# PHT_logger.net
KiCad netlist of a schematic drawn in EAGLE
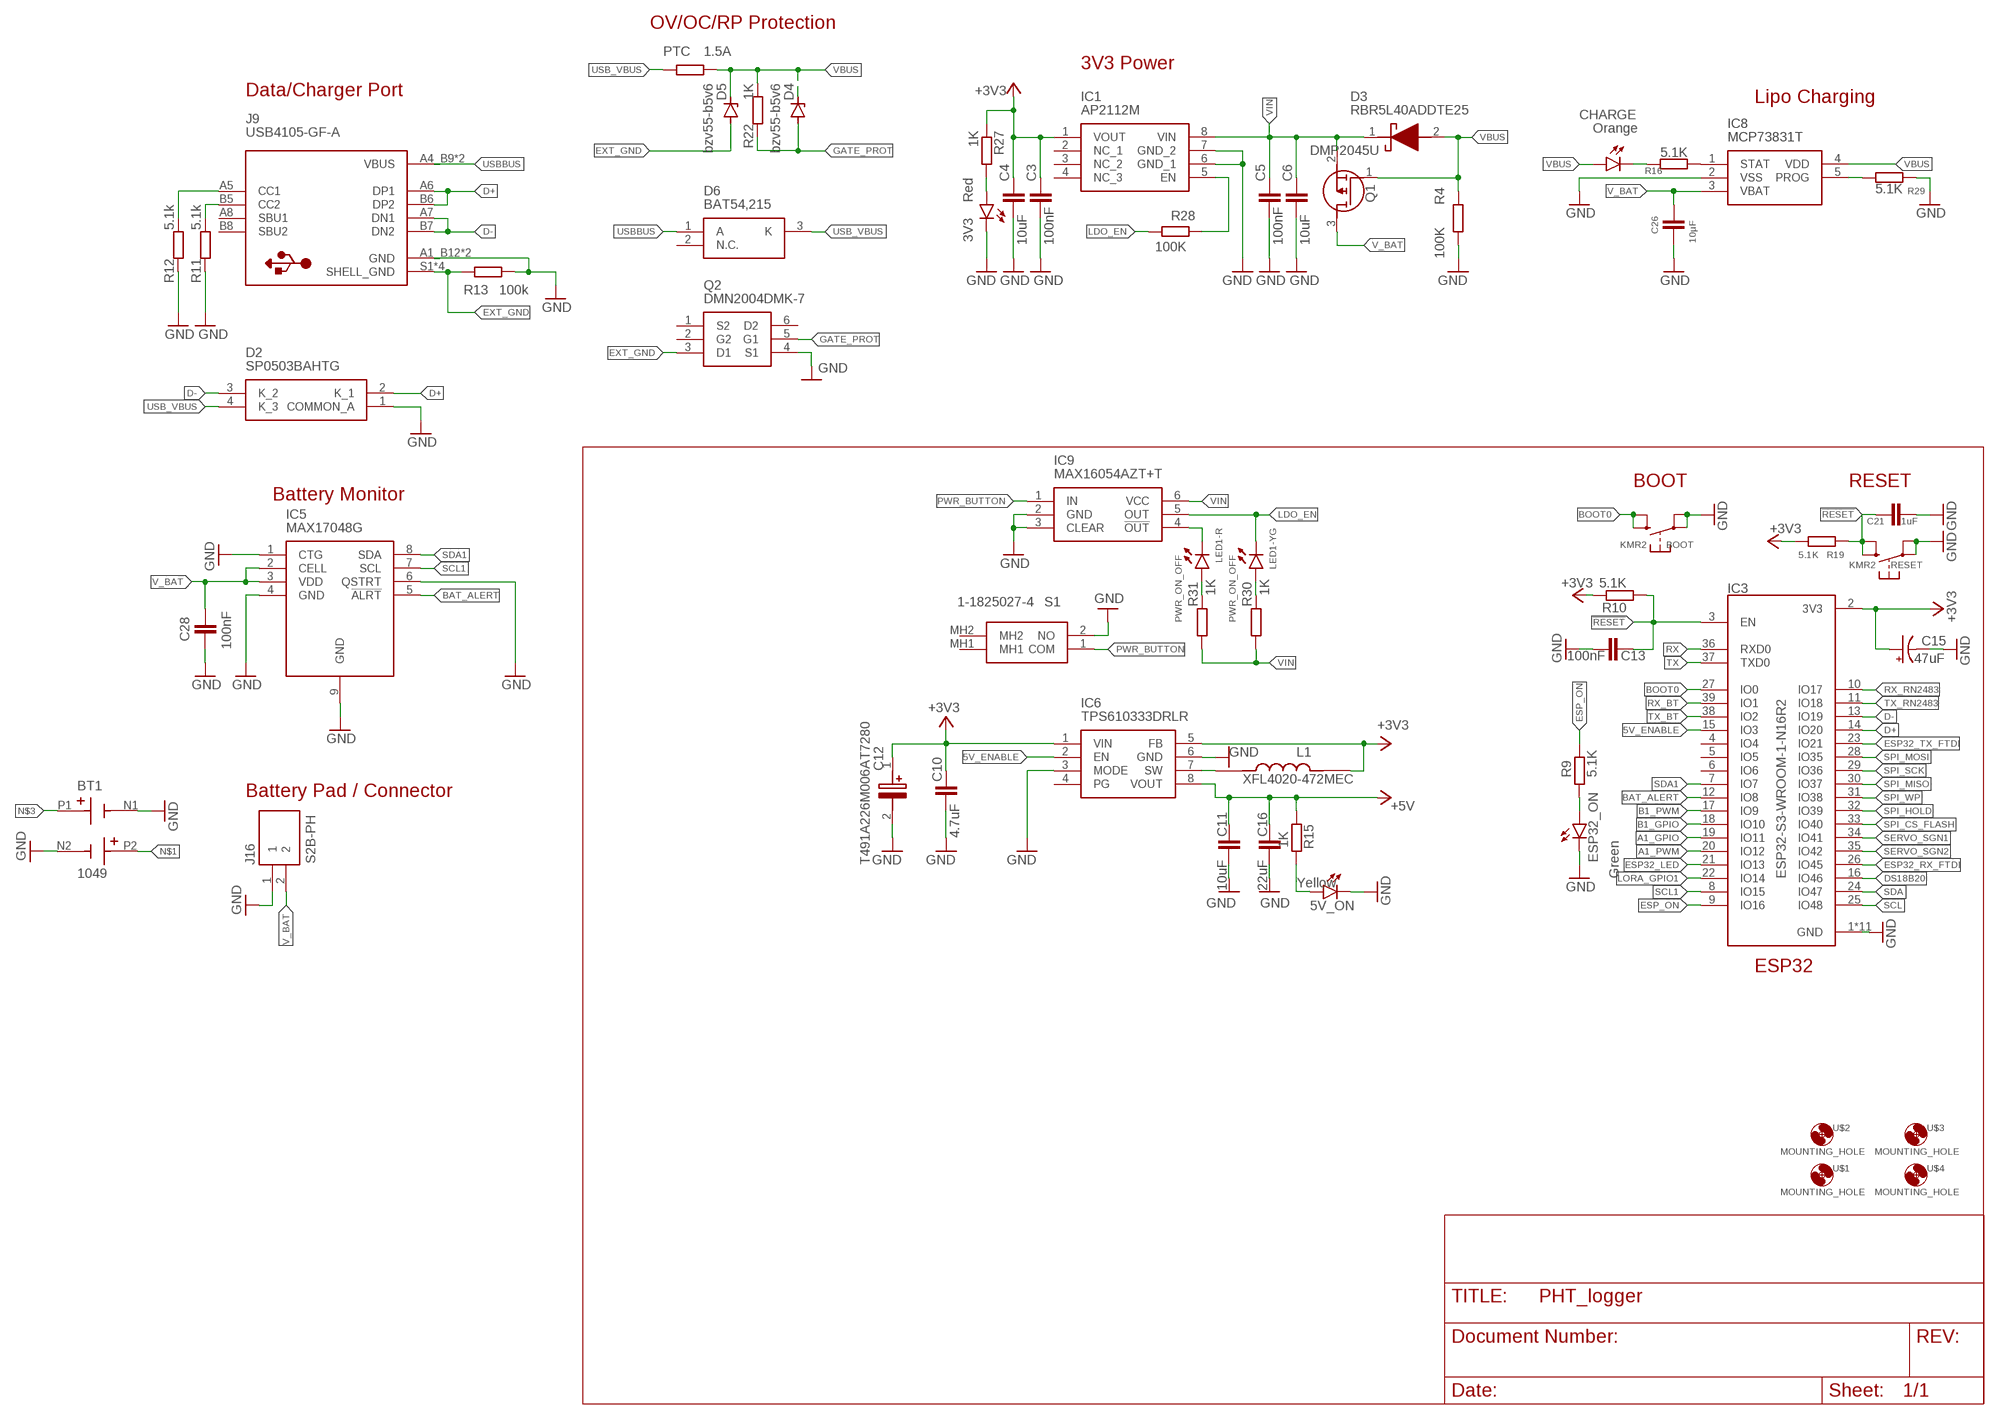
[diagram p0: schematic, sheet 1]

(export (version "E")
  (design (tool "Eeschema 10.0.6"))
  (components
    (comp (ref "3V3")
      (value "Red")
      (footprint "eagle-import:CHIPLED_0805")
      (libsource (lib "eagle-import") (part "LEDCHIPLED_0805"))
    )
    (comp (ref "5V_ON")
      (value "Yellow")
      (footprint "eagle-import:CHIPLED_0805")
      (libsource (lib "eagle-import") (part "LEDCHIPLED_0805"))
    )
    (comp (ref "BOOT")
      (value "KMR2")
      (footprint "eagle-import:BTN_KMR2_4.6X2.8")
      (libsource (lib "eagle-import") (part "SWITCH_TACT_SMT4.6X2.8"))
    )
    (comp (ref "BT1")
      (value "1049")
      (footprint "eagle-import:BAT_1049")
      (fields (field (name "MF") "Keystone Electronics"))
      (libsource (lib "eagle-import") (part "1049"))
    )
    (comp (ref "C3")
      (value "100nF")
      (footprint "eagle-import:C0603")
      (libsource (lib "eagle-import") (part "C-EUC0603"))
    )
    (comp (ref "C4")
      (value "10uF")
      (footprint "eagle-import:C0603")
      (libsource (lib "eagle-import") (part "C-EUC0603"))
    )
    (comp (ref "C5")
      (value "100nF")
      (footprint "eagle-import:C0603")
      (libsource (lib "eagle-import") (part "C-EUC0603"))
    )
    (comp (ref "C6")
      (value "10uF")
      (footprint "eagle-import:C0603")
      (libsource (lib "eagle-import") (part "C-EUC0603"))
    )
    (comp (ref "C10")
      (value "4.7uF")
      (footprint "eagle-import:C0805")
      (libsource (lib "eagle-import") (part "C-EUC0805"))
    )
    (comp (ref "C11")
      (value "10uF")
      (footprint "eagle-import:C0805")
      (libsource (lib "eagle-import") (part "C-EUC0805"))
    )
    (comp (ref "C12")
      (value "T491A226M006AT7280")
      (footprint "eagle-import:T491A")
      (libsource (lib "eagle-import") (part "T491A226M006AT7280"))
    )
    (comp (ref "C13")
      (value "100nF")
      (footprint "eagle-import:C0603")
      (libsource (lib "eagle-import") (part "C-EUC0603"))
    )
    (comp (ref "C15")
      (value "47uF")
      (footprint "eagle-import:CAPMP6032X250N")
      (fields (field (name "MF") "Vishay") (field (name "MP") "293D226X9025C2TE3"))
      (libsource (lib "eagle-import") (part "293D226X9025C2TE3"))
    )
    (comp (ref "C16")
      (value "22uF")
      (footprint "eagle-import:C0805")
      (libsource (lib "eagle-import") (part "C-EUC0805"))
    )
    (comp (ref "C21")
      (value "1uF")
      (footprint "eagle-import:C0603")
      (libsource (lib "eagle-import") (part "C-EUC0603"))
    )
    (comp (ref "C26")
      (value "10µF")
      (footprint "eagle-import:C0603K")
      (libsource (lib "eagle-import") (part "C-EUC0603K"))
    )
    (comp (ref "C28")
      (value "100nF")
      (footprint "eagle-import:C0603")
      (libsource (lib "eagle-import") (part "C-EUC0603"))
    )
    (comp (ref "CHARGE")
      (value "Orange")
      (footprint "eagle-import:CHIPLED_0805")
      (libsource (lib "eagle-import") (part "LEDCHIPLED_0805"))
    )
    (comp (ref "D2")
      (value "SP0503BAHTG")
      (footprint "eagle-import:SP0503BAHTG")
      (fields (field (name "MOUSER_PART_NUMBER") "576-SP0503BAHTG"))
      (libsource (lib "eagle-import") (part "SP0503BAHTG"))
    )
    (comp (ref "D3")
      (value "RBR5L40ADDTE25")
      (footprint "eagle-import:DIOM5026X220N")
      (fields (field (name "MOUSER_PART_NUMBER") "755-RBR5L40ADDTE25"))
      (libsource (lib "eagle-import") (part "RBR5L40ADDTE25"))
    )
    (comp (ref "D4")
      (value "bzv55-b5v6")
      (footprint "eagle-import:SOD80C")
      (libsource (lib "eagle-import") (part "ZENER-DIODESOD80C"))
    )
    (comp (ref "D5")
      (value "bzv55-b5v6")
      (footprint "eagle-import:SOD80C")
      (libsource (lib "eagle-import") (part "ZENER-DIODESOD80C"))
    )
    (comp (ref "D6")
      (value "BAT54,215")
      (footprint "eagle-import:SOT95P230X110-3N")
      (fields (field (name "MOUSER_PART_NUMBER") "771-BAT54-T/R"))
      (libsource (lib "eagle-import") (part "BAT54,215"))
    )
    (comp (ref "ESP32_ON")
      (value "Green")
      (footprint "eagle-import:CHIPLED_0805")
      (libsource (lib "eagle-import") (part "LEDCHIPLED_0805"))
    )
    (comp (ref "IC1")
      (value "AP2112M")
      (footprint "eagle-import:SOIC127P600X170-8N")
      (fields
        (field (name "MANUFACTURER_PART_NUMBER") "AP2112M-3.3TRG1")
        (field (name "MOUSER_PART_NUMBER") "621-AP2112M-3.3TRG1")
      )
      (libsource (lib "eagle-import") (part "AP2112M-3.3TRG1"))
    )
    (comp (ref "IC3")
      (value "ESP32-S3-WROOM-1-N16R2")
      (footprint "eagle-import:XCVR_ESP32-S3-WROOM-1-N16R2")
      (fields (field (name "MF") "Espressif Systems") (field (name "SPICEPREFIX") "X"))
      (libsource (lib "eagle-import") (part "ESP32-S3-WROOM-1-N16R2"))
    )
    (comp (ref "IC5")
      (value "MAX17048G")
      (footprint "eagle-import:SON50P200X200X80-9N")
      (fields
        (field (name "MANUFACTURER_PART_NUMBER") "MAX17048G+T10")
        (field (name "MOUSER_PART_NUMBER") "700-MAX17048G+T10")
      )
      (libsource (lib "eagle-import") (part "MAX17048G+T10"))
    )
    (comp (ref "IC6")
      (value "TPS610333DRLR")
      (footprint "eagle-import:SOTFL50P160X60-8N")
      (fields (field (name "MOUSER_PART_NUMBER") "595-TPS610333DRLR"))
      (libsource (lib "eagle-import") (part "TPS610333DRLR"))
    )
    (comp (ref "IC8")
      (value "MCP73831T")
      (footprint "eagle-import:SOT95P270X145-5N")
      (fields
        (field (name "MANUFACTURER_PART_NUMBER") "MCP73831T-2ACI/OT")
        (field (name "MOUSER_PART_NUMBER") "579-MCP73831T-2ACIOT")
      )
      (libsource (lib "eagle-import") (part "MCP73831T-2ACI_OT"))
    )
    (comp (ref "IC9")
      (value "MAX16054AZT+T")
      (footprint "eagle-import:SOT95P275X110-6N")
      (fields (field (name "MOUSER_PART_NUMBER") "700-MAX16054AZTT"))
      (libsource (lib "eagle-import") (part "MAX16054AZT+T"))
    )
    (comp (ref "J9")
      (value "USB4105-GF-A")
      (footprint "eagle-import:GCT_USB4105-GF-A")
      (fields (field (name "MF") "GCT"))
      (libsource (lib "eagle-import") (part "USB4105-GF-A"))
    )
    (comp (ref "J16")
      (value "S2B-PH")
      (footprint "eagle-import:JST_S2B-PH-K-S(LF)(SN)")
      (fields (field (name "MF") "JST Sales America Inc.") (field (name "MP") "S2B-PH-K-S(LF)(SN)"))
      (libsource (lib "eagle-import") (part "S2B-PH-K-S(LF)(SN)"))
    )
    (comp (ref "L1")
      (value "XFL4020-472MEC")
      (footprint "eagle-import:IND_XFL4020-472MEC")
      (fields (field (name "MF") "Coilcraft"))
      (libsource (lib "eagle-import") (part "XFL4020-472MEC"))
    )
    (comp (ref "LED1")
      (value "PWR_ON_OFF")
      (footprint "eagle-import:3216(1206)-4")
      (fields (field (name "MF") "OptoSupply") (field (name "MP") "OSRG1206C1C"))
      (libsource (lib "eagle-import") (part "OSRG1206C1C"))
    )
    (comp (ref "PTC")
      (value "1.5A")
      (footprint "eagle-import:R2512")
      (libsource (lib "eagle-import") (part "R-EU_R2512"))
    )
    (comp (ref "Q1")
      (value "DMP2045U")
      (footprint "eagle-import:SOT96P240X110-3N")
      (fields
        (field (name "MANUFACTURER_PART_NUMBER") "DMP2045U-7")
        (field (name "MOUSER_PART_NUMBER") "621-DMP2045U-7")
      )
      (libsource (lib "eagle-import") (part "DMP2045U-7"))
    )
    (comp (ref "Q2")
      (value "DMN2004DMK-7")
      (footprint "eagle-import:SOT95P285X145-6N")
      (fields (field (name "MOUSER_PART_NUMBER") "621-DMN2004DMK-7"))
      (libsource (lib "eagle-import") (part "DMN2004DMK-7"))
    )
    (comp (ref "R4")
      (value "100K")
      (footprint "eagle-import:R0603")
      (libsource (lib "eagle-import") (part "R-EU_R0603"))
    )
    (comp (ref "R9")
      (value "5.1K")
      (footprint "eagle-import:R0603")
      (libsource (lib "eagle-import") (part "R-EU_R0603"))
    )
    (comp (ref "R10")
      (value "5.1K")
      (footprint "eagle-import:R0603")
      (libsource (lib "eagle-import") (part "R-EU_R0603"))
    )
    (comp (ref "R11")
      (value "5.1k")
      (footprint "eagle-import:R0603")
      (libsource (lib "eagle-import") (part "R-EU_R0603"))
    )
    (comp (ref "R12")
      (value "5.1k")
      (footprint "eagle-import:R0603")
      (libsource (lib "eagle-import") (part "R-EU_R0603"))
    )
    (comp (ref "R13")
      (value "100k")
      (footprint "eagle-import:R0603")
      (libsource (lib "eagle-import") (part "R-EU_R0603"))
    )
    (comp (ref "R15")
      (value "1K")
      (footprint "eagle-import:R0603")
      (libsource (lib "eagle-import") (part "R-EU_R0603"))
    )
    (comp (ref "R16")
      (value "5.1K")
      (footprint "eagle-import:R0603")
      (libsource (lib "eagle-import") (part "R-EU_R0603"))
    )
    (comp (ref "R19")
      (value "5.1K")
      (footprint "eagle-import:R0603")
      (libsource (lib "eagle-import") (part "R-EU_R0603"))
    )
    (comp (ref "R22")
      (value "1K")
      (footprint "eagle-import:R0603")
      (libsource (lib "eagle-import") (part "R-EU_R0603"))
    )
    (comp (ref "R27")
      (value "1K")
      (footprint "eagle-import:R0603")
      (libsource (lib "eagle-import") (part "R-EU_R0603"))
    )
    (comp (ref "R28")
      (value "100K")
      (footprint "eagle-import:R0603")
      (libsource (lib "eagle-import") (part "R-EU_R0603"))
    )
    (comp (ref "R29")
      (value "5.1K")
      (footprint "eagle-import:R0603")
      (libsource (lib "eagle-import") (part "R-EU_R0603"))
    )
    (comp (ref "R30")
      (value "1K")
      (footprint "eagle-import:R0603")
      (libsource (lib "eagle-import") (part "R-EU_R0603"))
    )
    (comp (ref "R31")
      (value "1K")
      (footprint "eagle-import:R0603")
      (libsource (lib "eagle-import") (part "R-EU_R0603"))
    )
    (comp (ref "RESET")
      (value "KMR2")
      (footprint "eagle-import:BTN_KMR2_4.6X2.8")
      (libsource (lib "eagle-import") (part "SWITCH_TACT_SMT4.6X2.8"))
    )
    (comp (ref "S1")
      (value "1-1825027-4")
      (footprint "eagle-import:118250274")
      (libsource (lib "eagle-import") (part "1-1825027-4"))
    )
    (comp (ref "U$1")
      (value "MOUNTING_HOLE")
      (footprint "eagle-import:MOUNTING_HOLE")
      (libsource (lib "eagle-import") (part "MOUNTING_HOLE"))
    )
    (comp (ref "U$2")
      (value "MOUNTING_HOLE")
      (footprint "eagle-import:MOUNTING_HOLE")
      (libsource (lib "eagle-import") (part "MOUNTING_HOLE"))
    )
    (comp (ref "U$3")
      (value "MOUNTING_HOLE")
      (footprint "eagle-import:MOUNTING_HOLE")
      (libsource (lib "eagle-import") (part "MOUNTING_HOLE"))
    )
    (comp (ref "U$4")
      (value "MOUNTING_HOLE")
      (footprint "eagle-import:MOUNTING_HOLE")
      (libsource (lib "eagle-import") (part "MOUNTING_HOLE"))
    )
  )
  (nets
    (net (code "1") (name "+3V3") (class "Default")
      (node (ref "C10") (pin "2") (pinfunction "2_2") (pintype "passive"))
      (node (ref "C12") (pin "1") (pinfunction "+_1") (pintype "bidirectional"))
      (node (ref "C15") (pin "1") (pinfunction "+_1") (pintype "passive"))
      (node (ref "C3") (pin "2") (pinfunction "2_2") (pintype "passive"))
      (node (ref "C4") (pin "2") (pinfunction "2_2") (pintype "passive"))
      (node (ref "IC1") (pin "1") (pinfunction "VOUT_1") (pintype "bidirectional"))
      (node (ref "IC3") (pin "2") (pinfunction "3V3_2") (pintype "power_in"))
      (node (ref "IC6") (pin "1") (pinfunction "VIN_1") (pintype "bidirectional"))
      (node (ref "IC6") (pin "5") (pinfunction "FB_5") (pintype "bidirectional"))
      (node (ref "L1") (pin "2") (pinfunction "2_2") (pintype "passive"))
      (node (ref "R10") (pin "2") (pinfunction "2_2") (pintype "passive"))
      (node (ref "R19") (pin "2") (pinfunction "2_2") (pintype "passive"))
      (node (ref "R27") (pin "1") (pinfunction "1_1") (pintype "passive"))
    )
    (net (code "2") (name "+5V") (class "Default")
      (node (ref "C11") (pin "2") (pinfunction "2_2") (pintype "passive"))
      (node (ref "C16") (pin "2") (pinfunction "2_2") (pintype "passive"))
      (node (ref "IC6") (pin "8") (pinfunction "VOUT_8") (pintype "bidirectional"))
      (node (ref "R15") (pin "1") (pinfunction "1_1") (pintype "passive"))
    )
    (net (code "3") (name "/~{RESET}") (class "Default")
      (node (ref "C13") (pin "1") (pinfunction "1_1") (pintype "passive"))
      (node (ref "C21") (pin "1") (pinfunction "1_1") (pintype "passive"))
      (node (ref "IC3") (pin "3") (pinfunction "EN_3") (pintype "input"))
      (node (ref "R10") (pin "1") (pinfunction "1_1") (pintype "passive"))
      (node (ref "R19") (pin "1") (pinfunction "1_1") (pintype "passive"))
      (node (ref "RESET") (pin "B") (pinfunction "S_B") (pintype "passive"))
      (node (ref "RESET") (pin "B'") (pinfunction "S1_B'") (pintype "passive"))
    )
    (net (code "4") (name "5V_ENABLE") (class "Default")
      (node (ref "IC3") (pin "15") (pinfunction "IO3_15") (pintype "bidirectional"))
      (node (ref "IC6") (pin "2") (pinfunction "EN_2") (pintype "bidirectional"))
    )
    (net (code "5") (name "A1_GPIO") (class "Default")
      (node (ref "IC3") (pin "19") (pinfunction "IO11_19") (pintype "bidirectional"))
    )
    (net (code "6") (name "A1_PWM") (class "Default")
      (node (ref "IC3") (pin "20") (pinfunction "IO12_20") (pintype "bidirectional"))
    )
    (net (code "7") (name "B1_GPIO") (class "Default")
      (node (ref "IC3") (pin "18") (pinfunction "IO10_18") (pintype "bidirectional"))
    )
    (net (code "8") (name "B1_PWM") (class "Default")
      (node (ref "IC3") (pin "17") (pinfunction "IO9_17") (pintype "bidirectional"))
    )
    (net (code "9") (name "BAT_ALERT") (class "Default")
      (node (ref "IC3") (pin "12") (pinfunction "IO8_12") (pintype "bidirectional"))
      (node (ref "IC5") (pin "5") (pinfunction "~{ALRT}_5") (pintype "bidirectional"))
    )
    (net (code "10") (name "BOOT0") (class "Default")
      (node (ref "BOOT") (pin "B") (pinfunction "S_B") (pintype "passive"))
      (node (ref "BOOT") (pin "B'") (pinfunction "S1_B'") (pintype "passive"))
      (node (ref "IC3") (pin "27") (pinfunction "IO0_27") (pintype "bidirectional"))
    )
    (net (code "11") (name "D+") (class "Default")
      (node (ref "D2") (pin "2") (pinfunction "K_1_2") (pintype "bidirectional"))
      (node (ref "IC3") (pin "14") (pinfunction "IO20_14") (pintype "bidirectional"))
      (node (ref "J9") (pin "A6") (pinfunction "DP1_A6") (pintype "bidirectional"))
      (node (ref "J9") (pin "B6") (pinfunction "DP2_B6") (pintype "bidirectional"))
    )
    (net (code "12") (name "D-") (class "Default")
      (node (ref "D2") (pin "3") (pinfunction "K_2_3") (pintype "bidirectional"))
      (node (ref "IC3") (pin "13") (pinfunction "IO19_13") (pintype "bidirectional"))
      (node (ref "J9") (pin "A7") (pinfunction "DN1_A7") (pintype "bidirectional"))
      (node (ref "J9") (pin "B7") (pinfunction "DN2_B7") (pintype "bidirectional"))
    )
    (net (code "13") (name "DS18B20") (class "Default")
      (node (ref "IC3") (pin "16") (pinfunction "IO46_16") (pintype "bidirectional"))
    )
    (net (code "14") (name "ESP32_LED") (class "Default")
      (node (ref "IC3") (pin "21") (pinfunction "IO13_21") (pintype "bidirectional"))
    )
    (net (code "15") (name "ESP32_RX_FTDI") (class "Default")
      (node (ref "IC3") (pin "26") (pinfunction "IO45_26") (pintype "bidirectional"))
    )
    (net (code "16") (name "ESP32_TX_FTDI") (class "Default")
      (node (ref "IC3") (pin "23") (pinfunction "IO21_23") (pintype "bidirectional"))
    )
    (net (code "17") (name "ESP_ON") (class "Default")
      (node (ref "IC3") (pin "9") (pinfunction "IO16_9") (pintype "bidirectional"))
      (node (ref "R9") (pin "2") (pinfunction "2_2") (pintype "passive"))
    )
    (net (code "18") (name "EXT_GND") (class "Default")
      (node (ref "D5") (pin "A") (pinfunction "A_A") (pintype "passive"))
      (node (ref "J9") (pin "S1") (pinfunction "SHELL_GND_S1") (pintype "power_in"))
      (node (ref "J9") (pin "S2") (pinfunction "SHELL_GND_S2") (pintype "power_in"))
      (node (ref "J9") (pin "S3") (pinfunction "SHELL_GND_S3") (pintype "power_in"))
      (node (ref "J9") (pin "S4") (pinfunction "SHELL_GND_S4") (pintype "power_in"))
      (node (ref "Q2") (pin "3") (pinfunction "D1_3") (pintype "bidirectional"))
      (node (ref "R13") (pin "2") (pinfunction "2_2") (pintype "passive"))
    )
    (net (code "19") (name "GATE_PROT") (class "Default")
      (node (ref "D4") (pin "A") (pinfunction "A_A") (pintype "passive"))
      (node (ref "Q2") (pin "5") (pinfunction "G1_5") (pintype "bidirectional"))
      (node (ref "R22") (pin "1") (pinfunction "1_1") (pintype "passive"))
    )
    (net (code "20") (name "GND") (class "Default")
      (node (ref "3V3") (pin "C") (pinfunction "C_C") (pintype "passive"))
      (node (ref "5V_ON") (pin "C") (pinfunction "C_C") (pintype "passive"))
      (node (ref "BOOT") (pin "A") (pinfunction "P_A") (pintype "passive"))
      (node (ref "BOOT") (pin "A'") (pinfunction "P1_A'") (pintype "passive"))
      (node (ref "BT1") (pin "N1") (pinfunction "NEG1_N1") (pintype "passive"))
      (node (ref "BT1") (pin "N2") (pinfunction "NEG2_N2") (pintype "passive"))
      (node (ref "C10") (pin "1") (pinfunction "1_1") (pintype "passive"))
      (node (ref "C11") (pin "1") (pinfunction "1_1") (pintype "passive"))
      (node (ref "C12") (pin "2") (pinfunction "-_2") (pintype "bidirectional"))
      (node (ref "C13") (pin "2") (pinfunction "2_2") (pintype "passive"))
      (node (ref "C15") (pin "2") (pinfunction "-_2") (pintype "passive"))
      (node (ref "C16") (pin "1") (pinfunction "1_1") (pintype "passive"))
      (node (ref "C21") (pin "2") (pinfunction "2_2") (pintype "passive"))
      (node (ref "C26") (pin "2") (pinfunction "2_2") (pintype "passive"))
      (node (ref "C28") (pin "2") (pinfunction "2_2") (pintype "passive"))
      (node (ref "C3") (pin "1") (pinfunction "1_1") (pintype "passive"))
      (node (ref "C4") (pin "1") (pinfunction "1_1") (pintype "passive"))
      (node (ref "C5") (pin "1") (pinfunction "1_1") (pintype "passive"))
      (node (ref "C6") (pin "1") (pinfunction "1_1") (pintype "passive"))
      (node (ref "D2") (pin "1") (pinfunction "COMMON_A_1") (pintype "bidirectional"))
      (node (ref "ESP32_ON") (pin "C") (pinfunction "C_C") (pintype "passive"))
      (node (ref "IC1") (pin "6") (pinfunction "GND_1_6") (pintype "bidirectional"))
      (node (ref "IC1") (pin "7") (pinfunction "GND_2_7") (pintype "bidirectional"))
      (node (ref "IC3") (pin "1") (pinfunction "GND_1") (pintype "power_in"))
      (node (ref "IC3") (pin "40") (pinfunction "GND_40") (pintype "power_in"))
      (node (ref "IC3") (pin "41_1") (pinfunction "GND_41_1") (pintype "power_in"))
      (node (ref "IC3") (pin "41_2") (pinfunction "GND_41_2") (pintype "power_in"))
      (node (ref "IC3") (pin "41_3") (pinfunction "GND_41_3") (pintype "power_in"))
      (node (ref "IC3") (pin "41_4") (pinfunction "GND_41_4") (pintype "power_in"))
      (node (ref "IC3") (pin "41_5") (pinfunction "GND_41_5") (pintype "power_in"))
      (node (ref "IC3") (pin "41_6") (pinfunction "GND_41_6") (pintype "power_in"))
      (node (ref "IC3") (pin "41_7") (pinfunction "GND_41_7") (pintype "power_in"))
      (node (ref "IC3") (pin "41_8") (pinfunction "GND_41_8") (pintype "power_in"))
      (node (ref "IC3") (pin "41_9") (pinfunction "GND_41_9") (pintype "power_in"))
      (node (ref "IC5") (pin "1") (pinfunction "CTG_1") (pintype "bidirectional"))
      (node (ref "IC5") (pin "4") (pinfunction "GND_4") (pintype "bidirectional"))
      (node (ref "IC5") (pin "6") (pinfunction "QSTRT_6") (pintype "bidirectional"))
      (node (ref "IC5") (pin "9") (pinfunction "GND_9") (pintype "bidirectional"))
      (node (ref "IC6") (pin "3") (pinfunction "MODE_3") (pintype "bidirectional"))
      (node (ref "IC6") (pin "6") (pinfunction "GND_6") (pintype "bidirectional"))
      (node (ref "IC8") (pin "2") (pinfunction "VSS_2") (pintype "bidirectional"))
      (node (ref "IC9") (pin "2") (pinfunction "GND_2") (pintype "bidirectional"))
      (node (ref "IC9") (pin "3") (pinfunction "CLEAR_3") (pintype "bidirectional"))
      (node (ref "J16") (pin "1") (pinfunction "1_1") (pintype "passive"))
      (node (ref "J9") (pin "A1_B12") (pinfunction "GND_A1_B12") (pintype "power_in"))
      (node (ref "J9") (pin "B1_A12") (pinfunction "GND_B1_A12") (pintype "power_in"))
      (node (ref "Q2") (pin "4") (pinfunction "S1_4") (pintype "bidirectional"))
      (node (ref "R11") (pin "1") (pinfunction "1_1") (pintype "passive"))
      (node (ref "R12") (pin "1") (pinfunction "1_1") (pintype "passive"))
      (node (ref "R13") (pin "1") (pinfunction "1_1") (pintype "passive"))
      (node (ref "R29") (pin "1") (pinfunction "1_1") (pintype "passive"))
      (node (ref "R4") (pin "2") (pinfunction "2_2") (pintype "passive"))
      (node (ref "RESET") (pin "A") (pinfunction "P_A") (pintype "passive"))
      (node (ref "RESET") (pin "A'") (pinfunction "P1_A'") (pintype "passive"))
      (node (ref "S1") (pin "2") (pinfunction "NO_2") (pintype "bidirectional"))
    )
    (net (code "21") (name "LDO_EN") (class "Default")
      (node (ref "IC9") (pin "5") (pinfunction "OUT_5") (pintype "bidirectional"))
      (node (ref "LED1") (pin "3") (pinfunction "C_3") (pintype "output"))
      (node (ref "R28") (pin "1") (pinfunction "1_1") (pintype "passive"))
    )
    (net (code "22") (name "LORA_GPIO1") (class "Default")
      (node (ref "IC3") (pin "22") (pinfunction "IO14_22") (pintype "bidirectional"))
    )
    (net (code "23") (name "N$1") (class "Default")
      (node (ref "BT1") (pin "P2") (pinfunction "POS2_P2") (pintype "passive"))
    )
    (net (code "24") (name "N$3") (class "Default")
      (node (ref "BT1") (pin "P1") (pinfunction "POS1_P1") (pintype "passive"))
    )
    (net (code "25") (name "Net-(3V3-PadA)") (class "Default")
      (node (ref "3V3") (pin "A") (pinfunction "A_A") (pintype "passive"))
      (node (ref "R27") (pin "2") (pinfunction "2_2") (pintype "passive"))
    )
    (net (code "26") (name "Net-(5V_ON-PadA)") (class "Default")
      (node (ref "5V_ON") (pin "A") (pinfunction "A_A") (pintype "passive"))
      (node (ref "R15") (pin "2") (pinfunction "2_2") (pintype "passive"))
    )
    (net (code "27") (name "Net-(CHARGE-PadC)") (class "Default")
      (node (ref "CHARGE") (pin "C") (pinfunction "C_C") (pintype "passive"))
      (node (ref "R16") (pin "1") (pinfunction "1_1") (pintype "passive"))
    )
    (net (code "28") (name "Net-(ESP32_ON-PadA)") (class "Default")
      (node (ref "ESP32_ON") (pin "A") (pinfunction "A_A") (pintype "passive"))
      (node (ref "R9") (pin "1") (pinfunction "1_1") (pintype "passive"))
    )
    (net (code "29") (name "Net-(IC1-EN)") (class "Default")
      (node (ref "IC1") (pin "5") (pinfunction "EN_5") (pintype "bidirectional"))
      (node (ref "R28") (pin "2") (pinfunction "2_2") (pintype "passive"))
    )
    (net (code "30") (name "Net-(IC6-SW)") (class "Default")
      (node (ref "IC6") (pin "7") (pinfunction "SW_7") (pintype "bidirectional"))
      (node (ref "L1") (pin "1") (pinfunction "1_1") (pintype "passive"))
    )
    (net (code "31") (name "Net-(IC8-PROG)") (class "Default")
      (node (ref "IC8") (pin "5") (pinfunction "PROG_5") (pintype "bidirectional"))
      (node (ref "R29") (pin "2") (pinfunction "2_2") (pintype "passive"))
    )
    (net (code "32") (name "Net-(IC8-STAT)") (class "Default")
      (node (ref "IC8") (pin "1") (pinfunction "STAT_1") (pintype "bidirectional"))
      (node (ref "R16") (pin "2") (pinfunction "2_2") (pintype "passive"))
    )
    (net (code "33") (name "Net-(IC9-~{OUT})") (class "Default")
      (node (ref "IC9") (pin "4") (pinfunction "~{OUT}_4") (pintype "bidirectional"))
      (node (ref "LED1") (pin "1") (pinfunction "C_1") (pintype "output"))
    )
    (net (code "34") (name "Net-(J9-CC1)") (class "Default")
      (node (ref "J9") (pin "A5") (pinfunction "CC1_A5") (pintype "bidirectional"))
      (node (ref "R12") (pin "2") (pinfunction "2_2") (pintype "passive"))
    )
    (net (code "35") (name "Net-(J9-CC2)") (class "Default")
      (node (ref "J9") (pin "B5") (pinfunction "CC2_B5") (pintype "bidirectional"))
      (node (ref "R11") (pin "2") (pinfunction "2_2") (pintype "passive"))
    )
    (net (code "36") (name "Net-(LED1A-A)") (class "Default")
      (node (ref "LED1") (pin "2") (pinfunction "A_2") (pintype "input"))
      (node (ref "R31") (pin "2") (pinfunction "2_2") (pintype "passive"))
    )
    (net (code "37") (name "Net-(LED1B-A)") (class "Default")
      (node (ref "LED1") (pin "4") (pinfunction "A_4") (pintype "input"))
      (node (ref "R30") (pin "2") (pinfunction "2_2") (pintype "passive"))
    )
    (net (code "38") (name "PWR_BUTTON") (class "Default")
      (node (ref "IC9") (pin "1") (pinfunction "IN_1") (pintype "bidirectional"))
      (node (ref "S1") (pin "1") (pinfunction "COM_1") (pintype "bidirectional"))
    )
    (net (code "39") (name "RX") (class "Default")
      (node (ref "IC3") (pin "36") (pinfunction "RXD0_36") (pintype "bidirectional"))
    )
    (net (code "40") (name "RX_BT") (class "Default")
      (node (ref "IC3") (pin "39") (pinfunction "IO1_39") (pintype "bidirectional"))
    )
    (net (code "41") (name "RX_RN2483") (class "Default")
      (node (ref "IC3") (pin "10") (pinfunction "IO17_10") (pintype "bidirectional"))
    )
    (net (code "42") (name "SCL") (class "Default")
      (node (ref "IC3") (pin "25") (pinfunction "IO48_25") (pintype "bidirectional"))
    )
    (net (code "43") (name "SCL1") (class "Default")
      (node (ref "IC3") (pin "8") (pinfunction "IO15_8") (pintype "bidirectional"))
      (node (ref "IC5") (pin "7") (pinfunction "SCL_7") (pintype "bidirectional"))
    )
    (net (code "44") (name "SDA") (class "Default")
      (node (ref "IC3") (pin "24") (pinfunction "IO47_24") (pintype "bidirectional"))
    )
    (net (code "45") (name "SDA1") (class "Default")
      (node (ref "IC3") (pin "7") (pinfunction "IO7_7") (pintype "bidirectional"))
      (node (ref "IC5") (pin "8") (pinfunction "SDA_8") (pintype "bidirectional"))
    )
    (net (code "46") (name "SERVO_SGN1") (class "Default")
      (node (ref "IC3") (pin "34") (pinfunction "IO41_34") (pintype "bidirectional"))
    )
    (net (code "47") (name "SERVO_SGN2") (class "Default")
      (node (ref "IC3") (pin "35") (pinfunction "IO42_35") (pintype "bidirectional"))
    )
    (net (code "48") (name "SPI_CS_FLASH") (class "Default")
      (node (ref "IC3") (pin "33") (pinfunction "IO40_33") (pintype "bidirectional"))
    )
    (net (code "49") (name "SPI_HOLD") (class "Default")
      (node (ref "IC3") (pin "32") (pinfunction "IO39_32") (pintype "bidirectional"))
    )
    (net (code "50") (name "SPI_MISO") (class "Default")
      (node (ref "IC3") (pin "30") (pinfunction "IO37_30") (pintype "bidirectional"))
    )
    (net (code "51") (name "SPI_MOSI") (class "Default")
      (node (ref "IC3") (pin "28") (pinfunction "IO35_28") (pintype "bidirectional"))
    )
    (net (code "52") (name "SPI_SCK") (class "Default")
      (node (ref "IC3") (pin "29") (pinfunction "IO36_29") (pintype "bidirectional"))
    )
    (net (code "53") (name "SPI_WP") (class "Default")
      (node (ref "IC3") (pin "31") (pinfunction "IO38_31") (pintype "bidirectional"))
    )
    (net (code "54") (name "TX") (class "Default")
      (node (ref "IC3") (pin "37") (pinfunction "TXD0_37") (pintype "bidirectional"))
    )
    (net (code "55") (name "TX_BT") (class "Default")
      (node (ref "IC3") (pin "38") (pinfunction "IO2_38") (pintype "bidirectional"))
    )
    (net (code "56") (name "TX_RN2483") (class "Default")
      (node (ref "IC3") (pin "11") (pinfunction "IO18_11") (pintype "bidirectional"))
    )
    (net (code "57") (name "USBBUS") (class "Default")
      (node (ref "D6") (pin "1") (pinfunction "A_1") (pintype "bidirectional"))
      (node (ref "J9") (pin "A4_B9") (pinfunction "VBUS_A4_B9") (pintype "power_in"))
      (node (ref "J9") (pin "B4_A9") (pinfunction "VBUS_B4_A9") (pintype "power_in"))
    )
    (net (code "58") (name "USB_VBUS") (class "Default")
      (node (ref "D2") (pin "4") (pinfunction "K_3_4") (pintype "bidirectional"))
      (node (ref "D6") (pin "3") (pinfunction "K_3") (pintype "bidirectional"))
      (node (ref "PTC") (pin "1") (pinfunction "1_1") (pintype "passive"))
    )
    (net (code "59") (name "VBUS") (class "Default")
      (node (ref "CHARGE") (pin "A") (pinfunction "A_A") (pintype "passive"))
      (node (ref "D3") (pin "2") (pinfunction "A_2") (pintype "bidirectional"))
      (node (ref "D4") (pin "C") (pinfunction "C_C") (pintype "passive"))
      (node (ref "D5") (pin "C") (pinfunction "C_C") (pintype "passive"))
      (node (ref "IC8") (pin "4") (pinfunction "VDD_4") (pintype "bidirectional"))
      (node (ref "PTC") (pin "2") (pinfunction "2_2") (pintype "passive"))
      (node (ref "Q1") (pin "1") (pinfunction "G_1") (pintype "bidirectional"))
      (node (ref "R22") (pin "2") (pinfunction "2_2") (pintype "passive"))
      (node (ref "R4") (pin "1") (pinfunction "1_1") (pintype "passive"))
    )
    (net (code "60") (name "VIN") (class "Default")
      (node (ref "C5") (pin "2") (pinfunction "2_2") (pintype "passive"))
      (node (ref "C6") (pin "2") (pinfunction "2_2") (pintype "passive"))
      (node (ref "D3") (pin "1") (pinfunction "K_1") (pintype "bidirectional"))
      (node (ref "IC1") (pin "8") (pinfunction "VIN_8") (pintype "bidirectional"))
      (node (ref "IC9") (pin "6") (pinfunction "VCC_6") (pintype "bidirectional"))
      (node (ref "Q1") (pin "2") (pinfunction "S_2") (pintype "bidirectional"))
      (node (ref "R30") (pin "1") (pinfunction "1_1") (pintype "passive"))
      (node (ref "R31") (pin "1") (pinfunction "1_1") (pintype "passive"))
    )
    (net (code "61") (name "V_BAT") (class "Default")
      (node (ref "C26") (pin "1") (pinfunction "1_1") (pintype "passive"))
      (node (ref "C28") (pin "1") (pinfunction "1_1") (pintype "passive"))
      (node (ref "IC5") (pin "2") (pinfunction "CELL_2") (pintype "bidirectional"))
      (node (ref "IC5") (pin "3") (pinfunction "VDD_3") (pintype "bidirectional"))
      (node (ref "IC8") (pin "3") (pinfunction "VBAT_3") (pintype "bidirectional"))
      (node (ref "J16") (pin "2") (pinfunction "2_2") (pintype "passive"))
      (node (ref "Q1") (pin "3") (pinfunction "D_3") (pintype "bidirectional"))
    )
    (net (code "62") (name "unconnected-(D6-N.C.-Pad2)") (class "Default")
      (node (ref "D6") (pin "2") (pinfunction "N.C._2") (pintype "no_connect"))
    )
    (net (code "63") (name "unconnected-(IC1-NC_1-Pad2)") (class "Default")
      (node (ref "IC1") (pin "2") (pinfunction "NC_1_2") (pintype "bidirectional"))
    )
    (net (code "64") (name "unconnected-(IC1-NC_2-Pad3)") (class "Default")
      (node (ref "IC1") (pin "3") (pinfunction "NC_2_3") (pintype "bidirectional"))
    )
    (net (code "65") (name "unconnected-(IC1-NC_3-Pad4)") (class "Default")
      (node (ref "IC1") (pin "4") (pinfunction "NC_3_4") (pintype "bidirectional"))
    )
    (net (code "66") (name "unconnected-(IC3-IO4-Pad4)") (class "Default")
      (node (ref "IC3") (pin "4") (pinfunction "IO4_4") (pintype "bidirectional"))
    )
    (net (code "67") (name "unconnected-(IC3-IO5-Pad5)") (class "Default")
      (node (ref "IC3") (pin "5") (pinfunction "IO5_5") (pintype "bidirectional"))
    )
    (net (code "68") (name "unconnected-(IC3-IO6-Pad6)") (class "Default")
      (node (ref "IC3") (pin "6") (pinfunction "IO6_6") (pintype "bidirectional"))
    )
    (net (code "69") (name "unconnected-(IC6-PG-Pad4)") (class "Default")
      (node (ref "IC6") (pin "4") (pinfunction "PG_4") (pintype "bidirectional"))
    )
    (net (code "70") (name "unconnected-(J9-SBU1-PadA8)") (class "Default")
      (node (ref "J9") (pin "A8") (pinfunction "SBU1_A8") (pintype "bidirectional"))
    )
    (net (code "71") (name "unconnected-(J9-SBU2-PadB8)") (class "Default")
      (node (ref "J9") (pin "B8") (pinfunction "SBU2_B8") (pintype "bidirectional"))
    )
    (net (code "72") (name "unconnected-(Q2-D2-Pad6)") (class "Default")
      (node (ref "Q2") (pin "6") (pinfunction "D2_6") (pintype "bidirectional"))
    )
    (net (code "73") (name "unconnected-(Q2-G2-Pad2)") (class "Default")
      (node (ref "Q2") (pin "2") (pinfunction "G2_2") (pintype "bidirectional"))
    )
    (net (code "74") (name "unconnected-(Q2-S2-Pad1)") (class "Default")
      (node (ref "Q2") (pin "1") (pinfunction "S2_1") (pintype "bidirectional"))
    )
    (net (code "75") (name "unconnected-(S1-PadMH1)") (class "Default")
      (node (ref "S1") (pin "MH1") (pinfunction "MH1_MH1") (pintype "bidirectional"))
    )
    (net (code "76") (name "unconnected-(S1-PadMH2)") (class "Default")
      (node (ref "S1") (pin "MH2") (pinfunction "MH2_MH2") (pintype "bidirectional"))
    )
  )
)
